# 1ff_adapter.net
KiCad netlist of a schematic drawn in Altium Designer
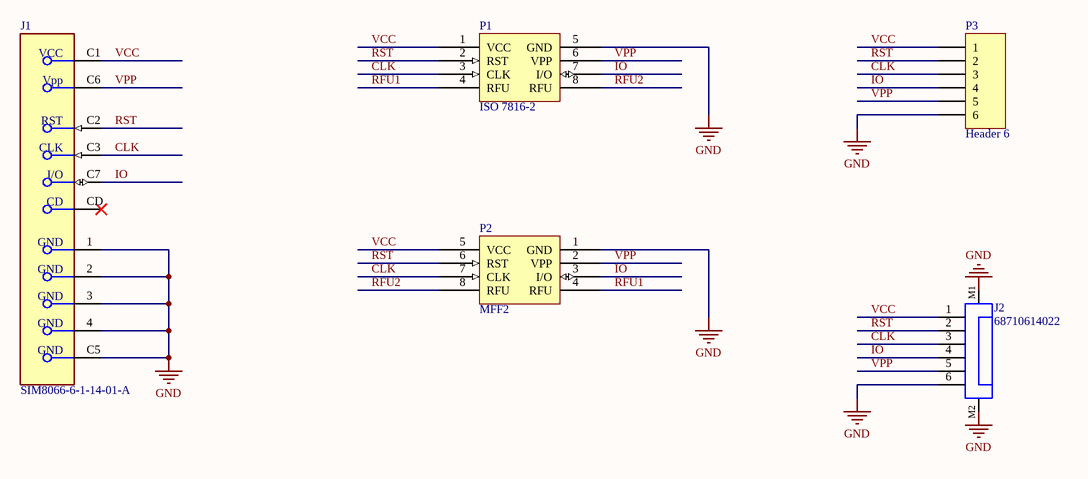
[diagram p0: 1ff_adapter.SchDoc]

(export (version "E")
  (design (tool "Eeschema 10.0.6"))
  (components
    (comp (ref "J1")
      (value "SIM8066-6-1-14-01-A")
      (footprint "FP-SIM8066-6-1-14-01-A-MFG")
      (description "SIM8066-6-1-14-01-A Memory Card Connectors 1.44mm Nano SIM Conn w/Peg and Switch")
      (libsource (lib "Altium Content Vault") (part "1421b091a134f49a34fd3b08e40bfdd"))
    )
    (comp (ref "J2")
      (value "68710614022")
      (footprint "68710614022")
      (libsource (lib "Altium Content Vault") (part "FPC - 06P - 2MP"))
    )
    (comp (ref "P1")
      (value "ISO 7816-2")
      (footprint "ISO 7816-2-Footprint-1")
      (libsource (lib "NyaMoe Internal Altium Server") (part "ISO 7816-2"))
    )
    (comp (ref "P2")
      (value "MFF2")
      (footprint "SON127P600-8N")
      (description "ETSI TS 102 671 V18.0.0 (2022-11) MFF2")
      (libsource (lib "NyaMoe Internal Altium Server") (part "MFF2"))
    )
    (comp (ref "P3")
      (value "Header 6")
      (footprint "HDR1X6")
      (description "Header, 6-Pin")
      (fields (field (name "PUBLISHER") "Altium Limited"))
      (libsource (lib "Miscellaneous Connectors") (part "Header 6"))
    )
  )
  (nets
    (net (code "1") (name "/CLK") (class "Default")
      (node (ref "J1") (pin "C3") (pinfunction "CLK_C3") (pintype "input"))
      (node (ref "J2") (pin "3") (pinfunction "3_3") (pintype "passive"))
      (node (ref "P1") (pin "3") (pinfunction "CLK_3") (pintype "input"))
      (node (ref "P2") (pin "7") (pinfunction "CLK_7") (pintype "input"))
      (node (ref "P3") (pin "3") (pinfunction "3_3") (pintype "passive"))
    )
    (net (code "2") (name "/IO") (class "Default")
      (node (ref "J1") (pin "C7") (pinfunction "I/O_C7") (pintype "bidirectional"))
      (node (ref "J2") (pin "4") (pinfunction "4_4") (pintype "passive"))
      (node (ref "P1") (pin "7") (pinfunction "I/O_7") (pintype "bidirectional"))
      (node (ref "P2") (pin "3") (pinfunction "I/O_3") (pintype "bidirectional"))
      (node (ref "P3") (pin "4") (pinfunction "4_4") (pintype "passive"))
    )
    (net (code "3") (name "/RFU1") (class "Default")
      (node (ref "P1") (pin "4") (pinfunction "RFU_4") (pintype "passive"))
      (node (ref "P2") (pin "4") (pinfunction "RFU_4") (pintype "passive"))
    )
    (net (code "4") (name "/RFU2") (class "Default")
      (node (ref "P1") (pin "8") (pinfunction "RFU_8") (pintype "passive"))
      (node (ref "P2") (pin "8") (pinfunction "RFU_8") (pintype "passive"))
    )
    (net (code "5") (name "/RST") (class "Default")
      (node (ref "J1") (pin "C2") (pinfunction "RST_C2") (pintype "input"))
      (node (ref "J2") (pin "2") (pinfunction "2_2") (pintype "passive"))
      (node (ref "P1") (pin "2") (pinfunction "RST_2") (pintype "input"))
      (node (ref "P2") (pin "6") (pinfunction "RST_6") (pintype "input"))
      (node (ref "P3") (pin "2") (pinfunction "2_2") (pintype "passive"))
    )
    (net (code "6") (name "/VCC") (class "Default")
      (node (ref "J1") (pin "C1") (pinfunction "VCC_C1") (pintype "power_in"))
      (node (ref "J2") (pin "1") (pinfunction "1_1") (pintype "passive"))
      (node (ref "P1") (pin "1") (pinfunction "VCC_1") (pintype "power_in"))
      (node (ref "P2") (pin "5") (pinfunction "VCC_5") (pintype "power_in"))
      (node (ref "P3") (pin "1") (pinfunction "1_1") (pintype "passive"))
    )
    (net (code "7") (name "/VPP") (class "Default")
      (node (ref "J1") (pin "C6") (pinfunction "Vpp_C6") (pintype "power_in"))
      (node (ref "J2") (pin "5") (pinfunction "5_5") (pintype "passive"))
      (node (ref "P1") (pin "6") (pinfunction "VPP_6") (pintype "power_in"))
      (node (ref "P2") (pin "2") (pinfunction "VPP_2") (pintype "power_in"))
      (node (ref "P3") (pin "5") (pinfunction "5_5") (pintype "passive"))
    )
    (net (code "8") (name "GND") (class "Default")
      (node (ref "J1") (pin "1") (pinfunction "GND_1") (pintype "power_in"))
      (node (ref "J1") (pin "2") (pinfunction "GND_2") (pintype "power_in"))
      (node (ref "J1") (pin "3") (pinfunction "GND_3") (pintype "power_in"))
      (node (ref "J1") (pin "4") (pinfunction "GND_4") (pintype "power_in"))
      (node (ref "J1") (pin "C5") (pinfunction "GND_C5") (pintype "power_in"))
      (node (ref "J2") (pin "6") (pinfunction "6_6") (pintype "passive"))
      (node (ref "J2") (pin "M1") (pinfunction "M1_M1") (pintype "passive"))
      (node (ref "J2") (pin "M2") (pinfunction "M2_M2") (pintype "passive"))
      (node (ref "P1") (pin "5") (pinfunction "GND_5") (pintype "power_in"))
      (node (ref "P2") (pin "1") (pinfunction "GND_1") (pintype "power_in"))
      (node (ref "P3") (pin "6") (pinfunction "6_6") (pintype "passive"))
    )
    (net (code "9") (name "unconnected-(J1-PadCD)") (class "Default")
      (node (ref "J1") (pin "CD") (pinfunction "CD_CD") (pintype "passive+no_connect"))
    )
  )
)
